# usb_current_monitor.net
KiCad netlist of a schematic drawn in EAGLE
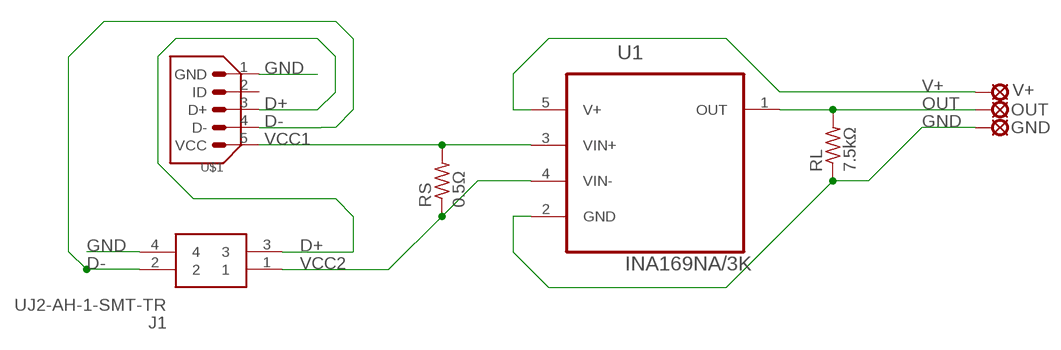
[diagram p0: schematic, sheet 1]

(export (version "E")
  (design (tool "Eeschema 10.0.6"))
  (components
    (comp (ref "GND")
      (value "LSP10")
      (footprint "eagle-import:LSP10")
      (libsource (lib "eagle-import") (part "LSP10"))
    )
    (comp (ref "J1")
      (value "UJ2-AH-1-SMT-TR")
      (footprint "eagle-import:UJ2-AH-1-SMT-TR")
      (libsource (lib "eagle-import") (part "UJ2-AH-1-SMT-TR"))
    )
    (comp (ref "OUT")
      (value "LSP10")
      (footprint "eagle-import:LSP10")
      (libsource (lib "eagle-import") (part "LSP10"))
    )
    (comp (ref "RL")
      (value "7.5kΩ")
      (footprint "eagle-import:R0603")
      (libsource (lib "eagle-import") (part "R-US_R0603"))
    )
    (comp (ref "RS")
      (value "0.5Ω")
      (footprint "eagle-import:R0603")
      (libsource (lib "eagle-import") (part "R-US_R0603"))
    )
    (comp (ref "U$1")
      (value "ZX62R-B-5P")
      (footprint "eagle-import:ZX62R-B-5P")
      (libsource (lib "eagle-import") (part "ZX62R-B-5P"))
    )
    (comp (ref "U1")
      (value "INA169NA/3K")
      (footprint "eagle-import:SOT95P280X145-5N")
      (fields (field (name "MF") "Texas Instruments"))
      (libsource (lib "eagle-import") (part "INA169NA/3K"))
    )
    (comp (ref "V+")
      (value "LSP10")
      (footprint "eagle-import:LSP10")
      (libsource (lib "eagle-import") (part "LSP10"))
    )
  )
  (nets
    (net (code "1") (name "/D+") (class "Default")
      (node (ref "J1") (pin "3") (pinfunction "3_3") (pintype "bidirectional"))
      (node (ref "U$1") (pin "3") (pinfunction "D+_3") (pintype "bidirectional"))
    )
    (net (code "2") (name "/D-") (class "Default")
      (node (ref "J1") (pin "2") (pinfunction "2_2") (pintype "bidirectional"))
      (node (ref "U$1") (pin "4") (pinfunction "D-_4") (pintype "bidirectional"))
    )
    (net (code "3") (name "/GND") (class "Default")
      (node (ref "GND") (pin "MP") (pinfunction "MP_MP") (pintype "passive"))
      (node (ref "J1") (pin "4") (pinfunction "4_4") (pintype "bidirectional"))
      (node (ref "RL") (pin "1") (pinfunction "1_1") (pintype "passive"))
      (node (ref "U$1") (pin "1") (pinfunction "GND_1") (pintype "passive"))
      (node (ref "U1") (pin "2") (pinfunction "GND_2") (pintype "passive"))
    )
    (net (code "4") (name "/OUT") (class "Default")
      (node (ref "OUT") (pin "MP") (pinfunction "MP_MP") (pintype "passive"))
      (node (ref "RL") (pin "2") (pinfunction "2_2") (pintype "passive"))
      (node (ref "U1") (pin "1") (pinfunction "OUT_1") (pintype "output"))
    )
    (net (code "5") (name "/V+") (class "Default")
      (node (ref "U1") (pin "5") (pinfunction "V+_5") (pintype "power_in"))
      (node (ref "V+") (pin "MP") (pinfunction "MP_MP") (pintype "passive"))
    )
    (net (code "6") (name "/VCC1") (class "Default")
      (node (ref "RS") (pin "2") (pinfunction "2_2") (pintype "passive"))
      (node (ref "U$1") (pin "5") (pinfunction "VCC_5") (pintype "power_in"))
      (node (ref "U1") (pin "3") (pinfunction "VIN+_3") (pintype "input"))
    )
    (net (code "7") (name "/VCC2") (class "Default")
      (node (ref "J1") (pin "1") (pinfunction "1_1") (pintype "bidirectional"))
      (node (ref "RS") (pin "1") (pinfunction "1_1") (pintype "passive"))
      (node (ref "U1") (pin "4") (pinfunction "VIN-_4") (pintype "input"))
    )
    (net (code "8") (name "unconnected-(U$1-ID-Pad2)") (class "Default")
      (node (ref "U$1") (pin "2") (pinfunction "ID_2") (pintype "bidirectional"))
    )
  )
)
